# main_board_ver_1.net
KiCad netlist of a schematic drawn in EAGLE
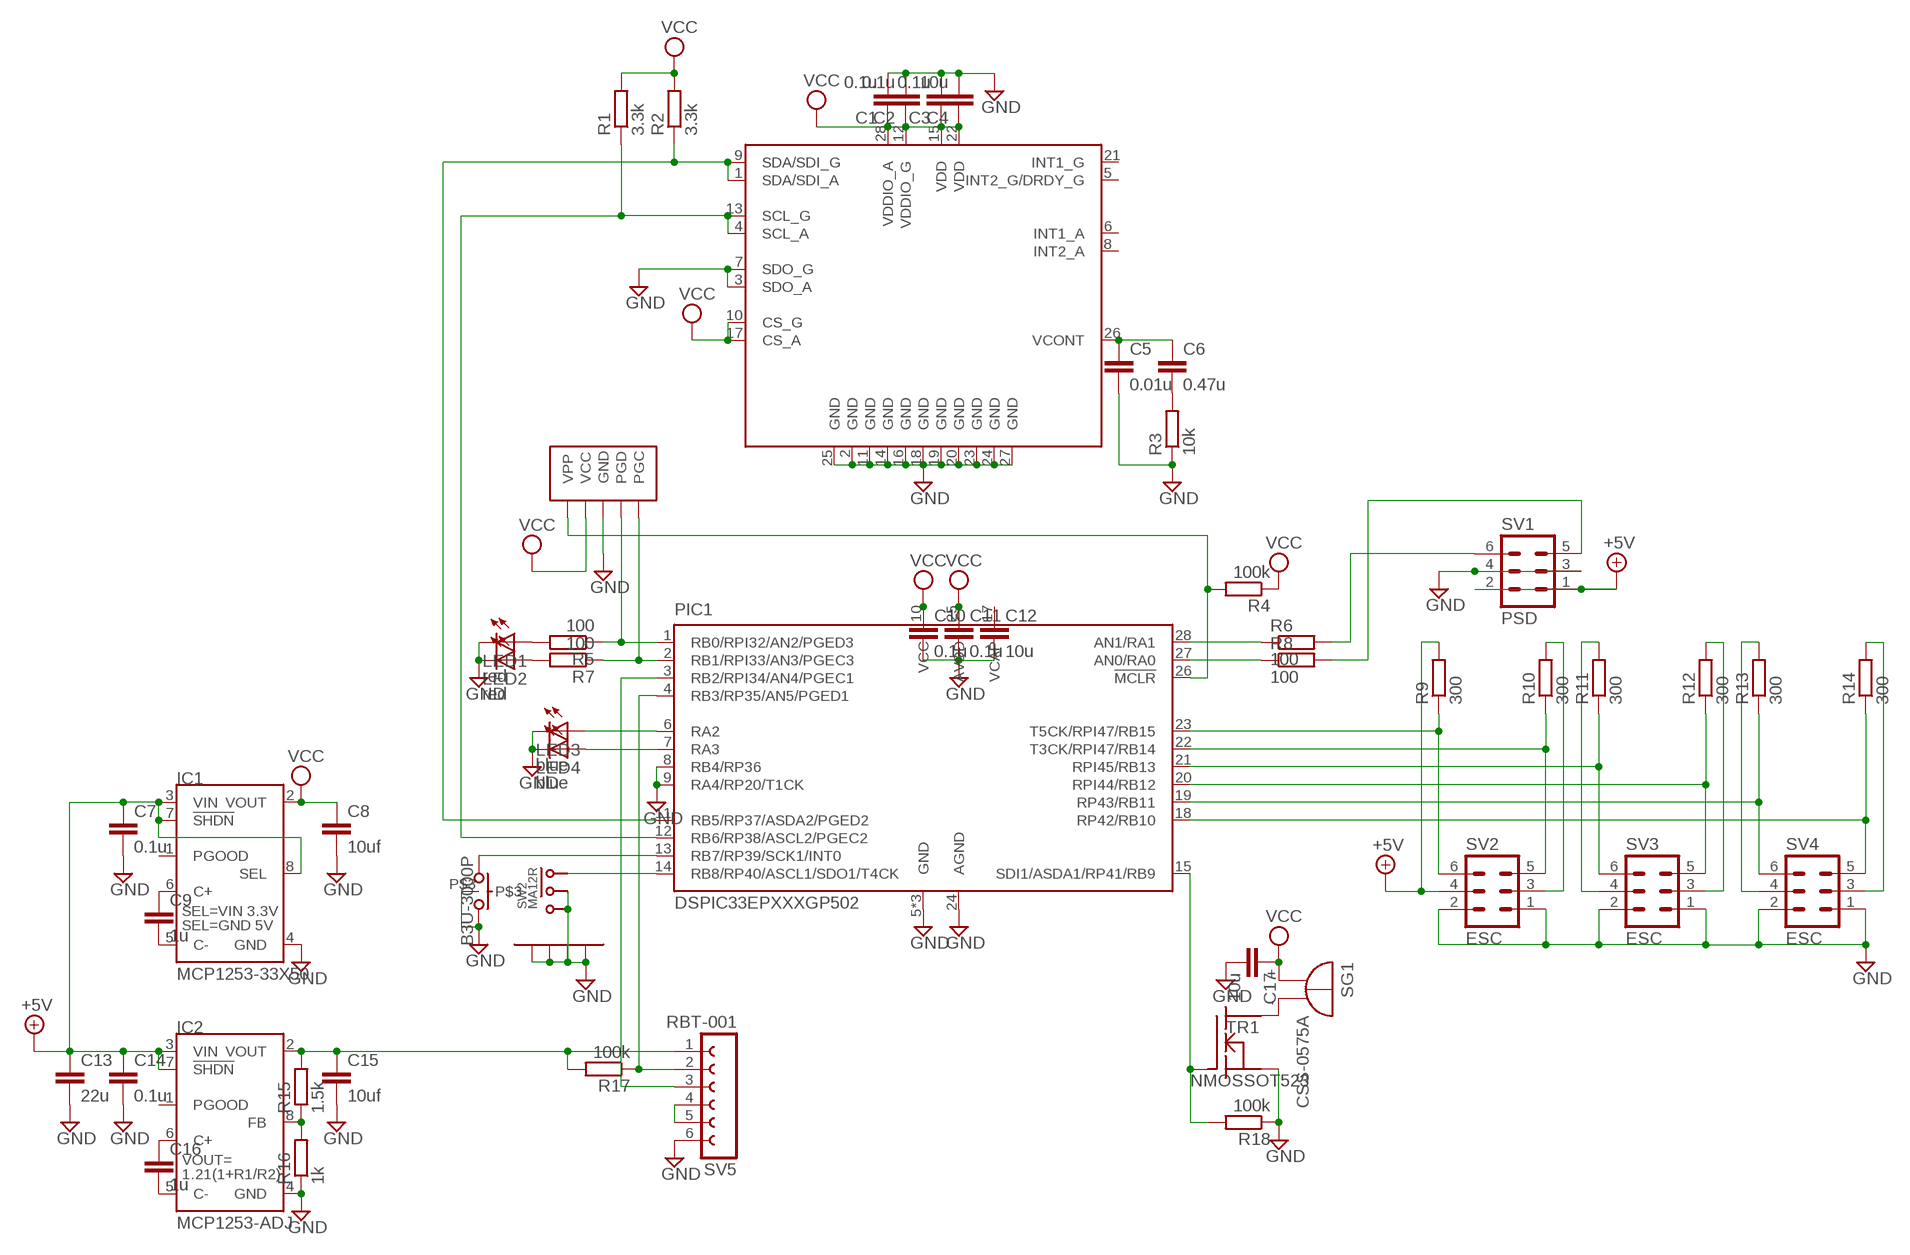
[diagram p0: schematic, sheet 1]

(export (version "E")
  (design (tool "Eeschema 10.0.6"))
  (components
    (comp (ref "C1")
      (value "0.1u")
      (footprint "eagle-import:C0402-SS")
      (libsource (lib "eagle-import") (part "C-EUC0402-SS"))
    )
    (comp (ref "C2")
      (value "0.1u")
      (footprint "eagle-import:C0402-SS")
      (libsource (lib "eagle-import") (part "C-EUC0402-SS"))
    )
    (comp (ref "C3")
      (value "0.1u")
      (footprint "eagle-import:C0402-SS")
      (libsource (lib "eagle-import") (part "C-EUC0402-SS"))
    )
    (comp (ref "C4")
      (value "10u")
      (footprint "eagle-import:C0805")
      (libsource (lib "eagle-import") (part "C-EUC0805"))
    )
    (comp (ref "C5")
      (value "0.01u")
      (footprint "eagle-import:C0402-SS")
      (libsource (lib "eagle-import") (part "C-EUC0402-SS"))
    )
    (comp (ref "C6")
      (value "0.47u")
      (footprint "eagle-import:C0402-SS")
      (libsource (lib "eagle-import") (part "C-EUC0402-SS"))
    )
    (comp (ref "C7")
      (value "0.1u")
      (footprint "eagle-import:C0402-SS")
      (libsource (lib "eagle-import") (part "C-EUC0402-SS"))
    )
    (comp (ref "C8")
      (value "10uf")
      (footprint "eagle-import:C0805")
      (libsource (lib "eagle-import") (part "C-EUC0805"))
    )
    (comp (ref "C9")
      (value "1u")
      (footprint "eagle-import:C0603")
      (libsource (lib "eagle-import") (part "C-EUC0603"))
    )
    (comp (ref "C10")
      (value "0.1u")
      (footprint "eagle-import:C0402-SS")
      (libsource (lib "eagle-import") (part "C-EUC0402-SS"))
    )
    (comp (ref "C11")
      (value "0.1u")
      (footprint "eagle-import:C0402-SS")
      (libsource (lib "eagle-import") (part "C-EUC0402-SS"))
    )
    (comp (ref "C12")
      (value "10u")
      (footprint "eagle-import:C0805")
      (libsource (lib "eagle-import") (part "C-EUC0805"))
    )
    (comp (ref "C13")
      (value "22u")
      (footprint "eagle-import:C1206")
      (libsource (lib "eagle-import") (part "C-EUC1206"))
    )
    (comp (ref "C14")
      (value "0.1u")
      (footprint "eagle-import:C0402-SS")
      (libsource (lib "eagle-import") (part "C-EUC0402-SS"))
    )
    (comp (ref "C15")
      (value "10uf")
      (footprint "eagle-import:C0805")
      (libsource (lib "eagle-import") (part "C-EUC0805"))
    )
    (comp (ref "C16")
      (value "1u")
      (footprint "eagle-import:C0603")
      (libsource (lib "eagle-import") (part "C-EUC0603"))
    )
    (comp (ref "C17")
      (value "10u")
      (footprint "eagle-import:C0805")
      (libsource (lib "eagle-import") (part "C-EUC0805"))
    )
    (comp (ref "IC1")
      (value "MCP1253-33X50")
      (footprint "eagle-import:MSOP8")
      (libsource (lib "eagle-import") (part "MCP1253-33X50"))
    )
    (comp (ref "IC2")
      (value "MCP1253-ADJ")
      (footprint "eagle-import:MSOP8")
      (libsource (lib "eagle-import") (part "MCP1253-ADJ"))
    )
    (comp (ref "IMU1")
      (value "LSM330DLRM")
      (footprint "eagle-import:LLGA28L(RM)")
      (libsource (lib "eagle-import") (part "LSM330DLRM"))
    )
    (comp (ref "LED1")
      (value "red")
      (footprint "eagle-import:CHIP-LED1005")
      (libsource (lib "eagle-import") (part "LED1005"))
    )
    (comp (ref "LED2")
      (value "red")
      (footprint "eagle-import:CHIP-LED1005")
      (libsource (lib "eagle-import") (part "LED1005"))
    )
    (comp (ref "LED3")
      (value "blue")
      (footprint "eagle-import:CHIP-LED1005")
      (libsource (lib "eagle-import") (part "LED1005"))
    )
    (comp (ref "LED4")
      (value "blue")
      (footprint "eagle-import:CHIP-LED1005")
      (libsource (lib "eagle-import") (part "LED1005"))
    )
    (comp (ref "PIC1")
      (value "DSPIC33EPXXXGP502")
      (footprint "eagle-import:QFN28-ML_6X6MM")
      (libsource (lib "eagle-import") (part "DSPIC33EPXXXGP502"))
    )
    (comp (ref "R1")
      (value "3.3k")
      (footprint "eagle-import:R0402-SS")
      (libsource (lib "eagle-import") (part "R-EU_R0402-SS"))
    )
    (comp (ref "R2")
      (value "3.3k")
      (footprint "eagle-import:R0402-SS")
      (libsource (lib "eagle-import") (part "R-EU_R0402-SS"))
    )
    (comp (ref "R3")
      (value "10k")
      (footprint "eagle-import:R0402-SS")
      (libsource (lib "eagle-import") (part "R-EU_R0402-SS"))
    )
    (comp (ref "R4")
      (value "100k")
      (footprint "eagle-import:R0402-SS")
      (libsource (lib "eagle-import") (part "R-EU_R0402-SS"))
    )
    (comp (ref "R5")
      (value "100")
      (footprint "eagle-import:R0402-SS")
      (libsource (lib "eagle-import") (part "R-EU_R0402-SS"))
    )
    (comp (ref "R6")
      (value "100")
      (footprint "eagle-import:R0402-SS")
      (libsource (lib "eagle-import") (part "R-EU_R0402-SS"))
    )
    (comp (ref "R7")
      (value "100")
      (footprint "eagle-import:R0402-SS")
      (libsource (lib "eagle-import") (part "R-EU_R0402-SS"))
    )
    (comp (ref "R8")
      (value "100")
      (footprint "eagle-import:R0402-SS")
      (libsource (lib "eagle-import") (part "R-EU_R0402-SS"))
    )
    (comp (ref "R9")
      (value "300")
      (footprint "eagle-import:R0402-SS")
      (libsource (lib "eagle-import") (part "R-EU_R0402-SS"))
    )
    (comp (ref "R10")
      (value "300")
      (footprint "eagle-import:R0402-SS")
      (libsource (lib "eagle-import") (part "R-EU_R0402-SS"))
    )
    (comp (ref "R11")
      (value "300")
      (footprint "eagle-import:R0402-SS")
      (libsource (lib "eagle-import") (part "R-EU_R0402-SS"))
    )
    (comp (ref "R12")
      (value "300")
      (footprint "eagle-import:R0402-SS")
      (libsource (lib "eagle-import") (part "R-EU_R0402-SS"))
    )
    (comp (ref "R13")
      (value "300")
      (footprint "eagle-import:R0402-SS")
      (libsource (lib "eagle-import") (part "R-EU_R0402-SS"))
    )
    (comp (ref "R14")
      (value "300")
      (footprint "eagle-import:R0402-SS")
      (libsource (lib "eagle-import") (part "R-EU_R0402-SS"))
    )
    (comp (ref "R15")
      (value "1.5k")
      (footprint "eagle-import:R0402-SS")
      (libsource (lib "eagle-import") (part "R-EU_R0402-SS"))
    )
    (comp (ref "R16")
      (value "1k")
      (footprint "eagle-import:R0402-SS")
      (libsource (lib "eagle-import") (part "R-EU_R0402-SS"))
    )
    (comp (ref "R17")
      (value "100k")
      (footprint "eagle-import:R0402-SS")
      (libsource (lib "eagle-import") (part "R-EU_R0402-SS"))
    )
    (comp (ref "R18")
      (value "100k")
      (footprint "eagle-import:R0402-SS")
      (libsource (lib "eagle-import") (part "R-EU_R0402-SS"))
    )
    (comp (ref "SG1")
      (value "CSS-0575A")
      (footprint "eagle-import:CSS-0575A")
      (libsource (lib "eagle-import") (part "CSS-0575A"))
    )
    (comp (ref "SV1")
      (value "PSD")
      (footprint "eagle-import:MA03-2")
      (libsource (lib "eagle-import") (part "MA03-2"))
    )
    (comp (ref "SV2")
      (value "ESC")
      (footprint "eagle-import:MA03-2")
      (libsource (lib "eagle-import") (part "MA03-2"))
    )
    (comp (ref "SV3")
      (value "ESC")
      (footprint "eagle-import:MA03-2")
      (libsource (lib "eagle-import") (part "MA03-2"))
    )
    (comp (ref "SV4")
      (value "ESC")
      (footprint "eagle-import:MA03-2")
      (libsource (lib "eagle-import") (part "MA03-2"))
    )
    (comp (ref "SV5")
      (value "RBT-001")
      (footprint "eagle-import:NPPN061BFLC")
      (libsource (lib "eagle-import") (part "FE06-1BFLC"))
    )
    (comp (ref "SW1")
      (value "B3U-3000P")
      (footprint "eagle-import:B3U-3000P")
      (libsource (lib "eagle-import") (part "B3U-3000P"))
    )
    (comp (ref "SW2")
      (value "MA12R")
      (footprint "eagle-import:MA12R")
      (libsource (lib "eagle-import") (part "MA12R"))
    )
    (comp (ref "TR1")
      (value "NMOSSOT523")
      (footprint "eagle-import:SOT523")
      (libsource (lib "eagle-import") (part "NMOSSOT523"))
    )
    (comp (ref "U$1")
      (value "ICSP")
      (footprint "eagle-import:MINI-ICSP")
      (libsource (lib "eagle-import") (part "ICSP"))
    )
  )
  (nets
    (net (code "1") (name "+5V") (class "Default")
      (node (ref "C13") (pin "1") (pinfunction "1_1") (pintype "passive"))
      (node (ref "C14") (pin "1") (pinfunction "1_1") (pintype "passive"))
      (node (ref "C7") (pin "1") (pinfunction "1_1") (pintype "passive"))
      (node (ref "IC1") (pin "3") (pinfunction "VIN_3") (pintype "power_in"))
      (node (ref "IC1") (pin "7") (pinfunction "~{SHDN}_7") (pintype "input"))
      (node (ref "IC1") (pin "8") (pinfunction "SEL_8") (pintype "input"))
      (node (ref "IC2") (pin "3") (pinfunction "VIN_3") (pintype "power_in"))
      (node (ref "IC2") (pin "7") (pinfunction "~{SHDN}_7") (pintype "input"))
      (node (ref "R9") (pin "2") (pinfunction "2_2") (pintype "passive"))
      (node (ref "SV1") (pin "1") (pinfunction "1_1") (pintype "passive"))
      (node (ref "SV1") (pin "2") (pinfunction "2_2") (pintype "passive"))
      (node (ref "SV2") (pin "4") (pinfunction "4_4") (pintype "passive"))
    )
    (net (code "2") (name "GND") (class "Default")
      (node (ref "C1") (pin "2") (pinfunction "2_2") (pintype "passive"))
      (node (ref "C10") (pin "2") (pinfunction "2_2") (pintype "passive"))
      (node (ref "C11") (pin "2") (pinfunction "2_2") (pintype "passive"))
      (node (ref "C12") (pin "2") (pinfunction "2_2") (pintype "passive"))
      (node (ref "C13") (pin "2") (pinfunction "2_2") (pintype "passive"))
      (node (ref "C14") (pin "2") (pinfunction "2_2") (pintype "passive"))
      (node (ref "C15") (pin "2") (pinfunction "2_2") (pintype "passive"))
      (node (ref "C17") (pin "2") (pinfunction "2_2") (pintype "passive"))
      (node (ref "C2") (pin "2") (pinfunction "2_2") (pintype "passive"))
      (node (ref "C3") (pin "2") (pinfunction "2_2") (pintype "passive"))
      (node (ref "C4") (pin "2") (pinfunction "2_2") (pintype "passive"))
      (node (ref "C5") (pin "2") (pinfunction "2_2") (pintype "passive"))
      (node (ref "C7") (pin "2") (pinfunction "2_2") (pintype "passive"))
      (node (ref "C8") (pin "2") (pinfunction "2_2") (pintype "passive"))
      (node (ref "IC1") (pin "4") (pinfunction "GND_4") (pintype "power_in"))
      (node (ref "IC2") (pin "4") (pinfunction "GND_4") (pintype "power_in"))
      (node (ref "IMU1") (pin "11") (pinfunction "GND_11") (pintype "power_in"))
      (node (ref "IMU1") (pin "14") (pinfunction "GND_14") (pintype "power_in"))
      (node (ref "IMU1") (pin "16") (pinfunction "GND_16") (pintype "power_in"))
      (node (ref "IMU1") (pin "18") (pinfunction "GND_18") (pintype "power_in"))
      (node (ref "IMU1") (pin "19") (pinfunction "GND_19") (pintype "power_in"))
      (node (ref "IMU1") (pin "2") (pinfunction "GND_2") (pintype "power_in"))
      (node (ref "IMU1") (pin "20") (pinfunction "GND_20") (pintype "power_in"))
      (node (ref "IMU1") (pin "23") (pinfunction "GND_23") (pintype "power_in"))
      (node (ref "IMU1") (pin "24") (pinfunction "GND_24") (pintype "power_in"))
      (node (ref "IMU1") (pin "25") (pinfunction "GND_25") (pintype "power_in"))
      (node (ref "IMU1") (pin "27") (pinfunction "GND_27") (pintype "power_in"))
      (node (ref "IMU1") (pin "3") (pinfunction "SDO_A_3") (pintype "output"))
      (node (ref "IMU1") (pin "7") (pinfunction "SDO_G_7") (pintype "output"))
      (node (ref "LED1") (pin "C") (pinfunction "C_C") (pintype "passive"))
      (node (ref "LED2") (pin "C") (pinfunction "C_C") (pintype "passive"))
      (node (ref "LED3") (pin "C") (pinfunction "C_C") (pintype "passive"))
      (node (ref "LED4") (pin "C") (pinfunction "C_C") (pintype "passive"))
      (node (ref "PIC1") (pin "16") (pinfunction "GND_16") (pintype "power_in"))
      (node (ref "PIC1") (pin "24") (pinfunction "AGND_24") (pintype "bidirectional"))
      (node (ref "PIC1") (pin "5") (pinfunction "GND_5") (pintype "power_in"))
      (node (ref "PIC1") (pin "8") (pinfunction "RB4/RP36_8") (pintype "bidirectional"))
      (node (ref "PIC1") (pin "9") (pinfunction "RA4/RP20/T1CK_9") (pintype "bidirectional"))
      (node (ref "PIC1") (pin "EXP") (pinfunction "GND_EXP") (pintype "power_in"))
      (node (ref "R16") (pin "1") (pinfunction "1_1") (pintype "passive"))
      (node (ref "R18") (pin "1") (pinfunction "1_1") (pintype "passive"))
      (node (ref "R3") (pin "1") (pinfunction "1_1") (pintype "passive"))
      (node (ref "SV1") (pin "3") (pinfunction "3_3") (pintype "passive"))
      (node (ref "SV1") (pin "4") (pinfunction "4_4") (pintype "passive"))
      (node (ref "SV2") (pin "1") (pinfunction "1_1") (pintype "passive"))
      (node (ref "SV2") (pin "2") (pinfunction "2_2") (pintype "passive"))
      (node (ref "SV3") (pin "1") (pinfunction "1_1") (pintype "passive"))
      (node (ref "SV3") (pin "2") (pinfunction "2_2") (pintype "passive"))
      (node (ref "SV4") (pin "1") (pinfunction "1_1") (pintype "passive"))
      (node (ref "SV4") (pin "2") (pinfunction "2_2") (pintype "passive"))
      (node (ref "SV5") (pin "6") (pinfunction "6_6") (pintype "passive"))
      (node (ref "SW1") (pin "P$2") (pinfunction "P$2_P$2") (pintype "passive"))
      (node (ref "SW1") (pin "P$3") (pinfunction "P$3_P$3") (pintype "passive"))
      (node (ref "SW2") (pin "P$2") (pinfunction "2_P$2") (pintype "bidirectional"))
      (node (ref "SW2") (pin "P$3") (pinfunction "3_P$3") (pintype "bidirectional"))
      (node (ref "SW2") (pin "P$4") (pinfunction "P$1_P$4") (pintype "bidirectional"))
      (node (ref "SW2") (pin "P$5") (pinfunction "P$2_P$5") (pintype "bidirectional"))
      (node (ref "SW2") (pin "P$6") (pinfunction "P$3_P$6") (pintype "bidirectional"))
      (node (ref "SW2") (pin "P$7") (pinfunction "P$4_P$7") (pintype "bidirectional"))
      (node (ref "TR1") (pin "2") (pinfunction "S_2") (pintype "bidirectional"))
      (node (ref "U$1") (pin "GND") (pinfunction "GND_GND") (pintype "power_in"))
    )
    (net (code "3") (name "Net-(C6-Pad2)") (class "Default")
      (node (ref "C6") (pin "2") (pinfunction "2_2") (pintype "passive"))
      (node (ref "R3") (pin "2") (pinfunction "2_2") (pintype "passive"))
    )
    (net (code "4") (name "Net-(IC1-C+)") (class "Default")
      (node (ref "C9") (pin "1") (pinfunction "1_1") (pintype "passive"))
      (node (ref "IC1") (pin "6") (pinfunction "C+_6") (pintype "passive"))
    )
    (net (code "5") (name "Net-(IC1-C-)") (class "Default")
      (node (ref "C9") (pin "2") (pinfunction "2_2") (pintype "passive"))
      (node (ref "IC1") (pin "5") (pinfunction "C-_5") (pintype "passive"))
    )
    (net (code "6") (name "Net-(IC2-C+)") (class "Default")
      (node (ref "C16") (pin "1") (pinfunction "1_1") (pintype "passive"))
      (node (ref "IC2") (pin "6") (pinfunction "C+_6") (pintype "passive"))
    )
    (net (code "7") (name "Net-(IC2-C-)") (class "Default")
      (node (ref "C16") (pin "2") (pinfunction "2_2") (pintype "passive"))
      (node (ref "IC2") (pin "5") (pinfunction "C-_5") (pintype "passive"))
    )
    (net (code "8") (name "Net-(IC2-FB)") (class "Default")
      (node (ref "IC2") (pin "8") (pinfunction "FB_8") (pintype "passive"))
      (node (ref "R15") (pin "1") (pinfunction "1_1") (pintype "passive"))
      (node (ref "R16") (pin "2") (pinfunction "2_2") (pintype "passive"))
    )
    (net (code "9") (name "Net-(IC2-VOUT)") (class "Default")
      (node (ref "C15") (pin "1") (pinfunction "1_1") (pintype "passive"))
      (node (ref "IC2") (pin "2") (pinfunction "VOUT_2") (pintype "output"))
      (node (ref "R15") (pin "2") (pinfunction "2_2") (pintype "passive"))
      (node (ref "R17") (pin "2") (pinfunction "2_2") (pintype "passive"))
      (node (ref "SV5") (pin "1") (pinfunction "1_1") (pintype "passive"))
    )
    (net (code "10") (name "Net-(IMU1-SCL_A)") (class "Default")
      (node (ref "IMU1") (pin "13") (pinfunction "SCL_G_13") (pintype "input"))
      (node (ref "IMU1") (pin "4") (pinfunction "SCL_A_4") (pintype "input"))
      (node (ref "PIC1") (pin "12") (pinfunction "RB6/RP38/ASCL2/PGEC2_12") (pintype "bidirectional"))
      (node (ref "R1") (pin "1") (pinfunction "1_1") (pintype "passive"))
    )
    (net (code "11") (name "Net-(IMU1-SDA{slash}SDI_A)") (class "Default")
      (node (ref "IMU1") (pin "1") (pinfunction "SDA/SDI_A_1") (pintype "bidirectional"))
      (node (ref "IMU1") (pin "9") (pinfunction "SDA/SDI_G_9") (pintype "bidirectional"))
      (node (ref "PIC1") (pin "11") (pinfunction "RB5/RP37/ASDA2/PGED2_11") (pintype "bidirectional"))
      (node (ref "R2") (pin "1") (pinfunction "1_1") (pintype "passive"))
    )
    (net (code "12") (name "Net-(IMU1-VCONT)") (class "Default")
      (node (ref "C5") (pin "1") (pinfunction "1_1") (pintype "passive"))
      (node (ref "C6") (pin "1") (pinfunction "1_1") (pintype "passive"))
      (node (ref "IMU1") (pin "26") (pinfunction "VCONT_26") (pintype "passive"))
    )
    (net (code "13") (name "Net-(LED1-PadA)") (class "Default")
      (node (ref "LED1") (pin "A") (pinfunction "A_A") (pintype "passive"))
      (node (ref "R5") (pin "2") (pinfunction "2_2") (pintype "passive"))
    )
    (net (code "14") (name "Net-(LED2-PadA)") (class "Default")
      (node (ref "LED2") (pin "A") (pinfunction "A_A") (pintype "passive"))
      (node (ref "R7") (pin "2") (pinfunction "2_2") (pintype "passive"))
    )
    (net (code "15") (name "Net-(PIC1-AN0{slash}RA0)") (class "Default")
      (node (ref "PIC1") (pin "27") (pinfunction "AN0/RA0_27") (pintype "bidirectional"))
      (node (ref "R8") (pin "1") (pinfunction "1_1") (pintype "passive"))
    )
    (net (code "16") (name "Net-(PIC1-AN1{slash}RA1)") (class "Default")
      (node (ref "PIC1") (pin "28") (pinfunction "AN1/RA1_28") (pintype "bidirectional"))
      (node (ref "R6") (pin "1") (pinfunction "1_1") (pintype "passive"))
    )
    (net (code "17") (name "Net-(PIC1-RA2)") (class "Default")
      (node (ref "LED3") (pin "A") (pinfunction "A_A") (pintype "passive"))
      (node (ref "PIC1") (pin "6") (pinfunction "RA2_6") (pintype "bidirectional"))
    )
    (net (code "18") (name "Net-(PIC1-RA3)") (class "Default")
      (node (ref "LED4") (pin "A") (pinfunction "A_A") (pintype "passive"))
      (node (ref "PIC1") (pin "7") (pinfunction "RA3_7") (pintype "bidirectional"))
    )
    (net (code "19") (name "Net-(PIC1-RB0{slash}RPI32{slash}AN2{slash}PGED3)") (class "Default")
      (node (ref "PIC1") (pin "1") (pinfunction "RB0/RPI32/AN2/PGED3_1") (pintype "bidirectional"))
      (node (ref "R5") (pin "1") (pinfunction "1_1") (pintype "passive"))
      (node (ref "U$1") (pin "PGD") (pinfunction "PGD_PGD") (pintype "bidirectional"))
    )
    (net (code "20") (name "Net-(PIC1-RB1{slash}RPI33{slash}AN3{slash}PGEC3)") (class "Default")
      (node (ref "PIC1") (pin "2") (pinfunction "RB1/RPI33/AN3/PGEC3_2") (pintype "bidirectional"))
      (node (ref "R7") (pin "1") (pinfunction "1_1") (pintype "passive"))
      (node (ref "U$1") (pin "PGC") (pinfunction "PGC_PGC") (pintype "output"))
    )
    (net (code "21") (name "Net-(PIC1-RB2{slash}RPI34{slash}AN4{slash}PGEC1)") (class "Default")
      (node (ref "PIC1") (pin "3") (pinfunction "RB2/RPI34/AN4/PGEC1_3") (pintype "bidirectional"))
      (node (ref "SV5") (pin "3") (pinfunction "3_3") (pintype "passive"))
    )
    (net (code "22") (name "Net-(PIC1-RB3{slash}RP35{slash}AN5{slash}PGED1)") (class "Default")
      (node (ref "PIC1") (pin "4") (pinfunction "RB3/RP35/AN5/PGED1_4") (pintype "bidirectional"))
      (node (ref "R17") (pin "1") (pinfunction "1_1") (pintype "passive"))
      (node (ref "SV5") (pin "2") (pinfunction "2_2") (pintype "passive"))
    )
    (net (code "23") (name "Net-(PIC1-RB7{slash}RP39{slash}SCK1{slash}INT0)") (class "Default")
      (node (ref "PIC1") (pin "13") (pinfunction "RB7/RP39/SCK1/INT0_13") (pintype "bidirectional"))
      (node (ref "SW1") (pin "P$1") (pinfunction "P$1_P$1") (pintype "passive"))
    )
    (net (code "24") (name "Net-(PIC1-RB8{slash}RP40{slash}ASCL1{slash}SDO1{slash}T4CK)") (class "Default")
      (node (ref "PIC1") (pin "14") (pinfunction "RB8/RP40/ASCL1/SDO1/T4CK_14") (pintype "bidirectional"))
      (node (ref "SW2") (pin "P$1") (pinfunction "1_P$1") (pintype "bidirectional"))
    )
    (net (code "25") (name "Net-(PIC1-RP42{slash}RB10)") (class "Default")
      (node (ref "PIC1") (pin "18") (pinfunction "RP42/RB10_18") (pintype "bidirectional"))
      (node (ref "R14") (pin "1") (pinfunction "1_1") (pintype "passive"))
      (node (ref "SV4") (pin "5") (pinfunction "5_5") (pintype "passive"))
    )
    (net (code "26") (name "Net-(PIC1-RP43{slash}RB11)") (class "Default")
      (node (ref "PIC1") (pin "19") (pinfunction "RP43/RB11_19") (pintype "bidirectional"))
      (node (ref "R13") (pin "1") (pinfunction "1_1") (pintype "passive"))
      (node (ref "SV4") (pin "6") (pinfunction "6_6") (pintype "passive"))
    )
    (net (code "27") (name "Net-(PIC1-RPI44{slash}RB12)") (class "Default")
      (node (ref "PIC1") (pin "20") (pinfunction "RPI44/RB12_20") (pintype "bidirectional"))
      (node (ref "R12") (pin "1") (pinfunction "1_1") (pintype "passive"))
      (node (ref "SV3") (pin "5") (pinfunction "5_5") (pintype "passive"))
    )
    (net (code "28") (name "Net-(PIC1-RPI45{slash}RB13)") (class "Default")
      (node (ref "PIC1") (pin "21") (pinfunction "RPI45/RB13_21") (pintype "bidirectional"))
      (node (ref "R11") (pin "1") (pinfunction "1_1") (pintype "passive"))
      (node (ref "SV3") (pin "6") (pinfunction "6_6") (pintype "passive"))
    )
    (net (code "29") (name "Net-(PIC1-SDI1{slash}ASDA1{slash}RP41{slash}RB9)") (class "Default")
      (node (ref "PIC1") (pin "15") (pinfunction "SDI1/ASDA1/RP41/RB9_15") (pintype "bidirectional"))
      (node (ref "R18") (pin "2") (pinfunction "2_2") (pintype "passive"))
      (node (ref "TR1") (pin "1") (pinfunction "G_1") (pintype "bidirectional"))
    )
    (net (code "30") (name "Net-(PIC1-T3CK{slash}RPI47{slash}RB14)") (class "Default")
      (node (ref "PIC1") (pin "22") (pinfunction "T3CK/RPI47/RB14_22") (pintype "bidirectional"))
      (node (ref "R10") (pin "1") (pinfunction "1_1") (pintype "passive"))
      (node (ref "SV2") (pin "5") (pinfunction "5_5") (pintype "passive"))
    )
    (net (code "31") (name "Net-(PIC1-T5CK{slash}RPI47{slash}RB15)") (class "Default")
      (node (ref "PIC1") (pin "23") (pinfunction "T5CK/RPI47/RB15_23") (pintype "bidirectional"))
      (node (ref "R9") (pin "1") (pinfunction "1_1") (pintype "passive"))
      (node (ref "SV2") (pin "6") (pinfunction "6_6") (pintype "passive"))
    )
    (net (code "32") (name "Net-(PIC1-VCAP)") (class "Default")
      (node (ref "C12") (pin "1") (pinfunction "1_1") (pintype "passive"))
      (node (ref "PIC1") (pin "17") (pinfunction "VCAP_17") (pintype "power_in"))
    )
    (net (code "33") (name "Net-(PIC1-~{MCLR})") (class "Default")
      (node (ref "PIC1") (pin "26") (pinfunction "~{MCLR}_26") (pintype "input"))
      (node (ref "R4") (pin "2") (pinfunction "2_2") (pintype "passive"))
      (node (ref "U$1") (pin "VPP") (pinfunction "VPP_VPP") (pintype "output"))
    )
    (net (code "34") (name "Net-(R6-Pad2)") (class "Default")
      (node (ref "R6") (pin "2") (pinfunction "2_2") (pintype "passive"))
      (node (ref "SV1") (pin "6") (pinfunction "6_6") (pintype "passive"))
    )
    (net (code "35") (name "Net-(R8-Pad2)") (class "Default")
      (node (ref "R8") (pin "2") (pinfunction "2_2") (pintype "passive"))
      (node (ref "SV1") (pin "5") (pinfunction "5_5") (pintype "passive"))
    )
    (net (code "36") (name "Net-(R10-Pad2)") (class "Default")
      (node (ref "R10") (pin "2") (pinfunction "2_2") (pintype "passive"))
      (node (ref "SV2") (pin "3") (pinfunction "3_3") (pintype "passive"))
    )
    (net (code "37") (name "Net-(R11-Pad2)") (class "Default")
      (node (ref "R11") (pin "2") (pinfunction "2_2") (pintype "passive"))
      (node (ref "SV3") (pin "4") (pinfunction "4_4") (pintype "passive"))
    )
    (net (code "38") (name "Net-(R12-Pad2)") (class "Default")
      (node (ref "R12") (pin "2") (pinfunction "2_2") (pintype "passive"))
      (node (ref "SV3") (pin "3") (pinfunction "3_3") (pintype "passive"))
    )
    (net (code "39") (name "Net-(R13-Pad2)") (class "Default")
      (node (ref "R13") (pin "2") (pinfunction "2_2") (pintype "passive"))
      (node (ref "SV4") (pin "4") (pinfunction "4_4") (pintype "passive"))
    )
    (net (code "40") (name "Net-(R14-Pad2)") (class "Default")
      (node (ref "R14") (pin "2") (pinfunction "2_2") (pintype "passive"))
      (node (ref "SV4") (pin "3") (pinfunction "3_3") (pintype "passive"))
    )
    (net (code "41") (name "Net-(SV5-Pad4)") (class "Default")
      (node (ref "SV5") (pin "4") (pinfunction "4_4") (pintype "passive"))
      (node (ref "SV5") (pin "5") (pinfunction "5_5") (pintype "passive"))
    )
    (net (code "42") (name "Net-(TR1-D)") (class "Default")
      (node (ref "SG1") (pin "-") (pinfunction "-_-") (pintype "passive"))
      (node (ref "TR1") (pin "3") (pinfunction "D_3") (pintype "bidirectional"))
    )
    (net (code "43") (name "VCC") (class "Default")
      (node (ref "C1") (pin "1") (pinfunction "1_1") (pintype "passive"))
      (node (ref "C10") (pin "1") (pinfunction "1_1") (pintype "passive"))
      (node (ref "C11") (pin "1") (pinfunction "1_1") (pintype "passive"))
      (node (ref "C17") (pin "1") (pinfunction "1_1") (pintype "passive"))
      (node (ref "C2") (pin "1") (pinfunction "1_1") (pintype "passive"))
      (node (ref "C3") (pin "1") (pinfunction "1_1") (pintype "passive"))
      (node (ref "C4") (pin "1") (pinfunction "1_1") (pintype "passive"))
      (node (ref "C8") (pin "1") (pinfunction "1_1") (pintype "passive"))
      (node (ref "IC1") (pin "2") (pinfunction "VOUT_2") (pintype "output"))
      (node (ref "IMU1") (pin "10") (pinfunction "CS_G_10") (pintype "input"))
      (node (ref "IMU1") (pin "12") (pinfunction "VDDIO_G_12") (pintype "power_in"))
      (node (ref "IMU1") (pin "15") (pinfunction "VDD_15") (pintype "power_in"))
      (node (ref "IMU1") (pin "17") (pinfunction "CS_A_17") (pintype "input"))
      (node (ref "IMU1") (pin "22") (pinfunction "VDD_22") (pintype "power_in"))
      (node (ref "IMU1") (pin "28") (pinfunction "VDDIO_A_28") (pintype "power_in"))
      (node (ref "PIC1") (pin "10") (pinfunction "VCC_10") (pintype "power_in"))
      (node (ref "PIC1") (pin "25") (pinfunction "AVDD_25") (pintype "bidirectional"))
      (node (ref "R1") (pin "2") (pinfunction "2_2") (pintype "passive"))
      (node (ref "R2") (pin "2") (pinfunction "2_2") (pintype "passive"))
      (node (ref "R4") (pin "1") (pinfunction "1_1") (pintype "passive"))
      (node (ref "SG1") (pin "+") (pinfunction "+_+") (pintype "passive"))
      (node (ref "U$1") (pin "VCC") (pinfunction "VCC_VCC") (pintype "power_in"))
    )
    (net (code "44") (name "unconnected-(IC1-PGOOD-Pad1)") (class "Default")
      (node (ref "IC1") (pin "1") (pinfunction "PGOOD_1") (pintype "open_collector"))
    )
    (net (code "45") (name "unconnected-(IC2-PGOOD-Pad1)") (class "Default")
      (node (ref "IC2") (pin "1") (pinfunction "PGOOD_1") (pintype "output"))
    )
    (net (code "46") (name "unconnected-(IMU1-INT1_A-Pad6)") (class "Default")
      (node (ref "IMU1") (pin "6") (pinfunction "INT1_A_6") (pintype "output"))
    )
    (net (code "47") (name "unconnected-(IMU1-INT1_G-Pad21)") (class "Default")
      (node (ref "IMU1") (pin "21") (pinfunction "INT1_G_21") (pintype "output"))
    )
    (net (code "48") (name "unconnected-(IMU1-INT2_A-Pad8)") (class "Default")
      (node (ref "IMU1") (pin "8") (pinfunction "INT2_A_8") (pintype "output"))
    )
    (net (code "49") (name "unconnected-(IMU1-INT2_G{slash}DRDY_G-Pad5)") (class "Default")
      (node (ref "IMU1") (pin "5") (pinfunction "INT2_G/DRDY_G_5") (pintype "output"))
    )
  )
)
